# TapuinoMini.net
KiCad netlist of a schematic drawn in EAGLE
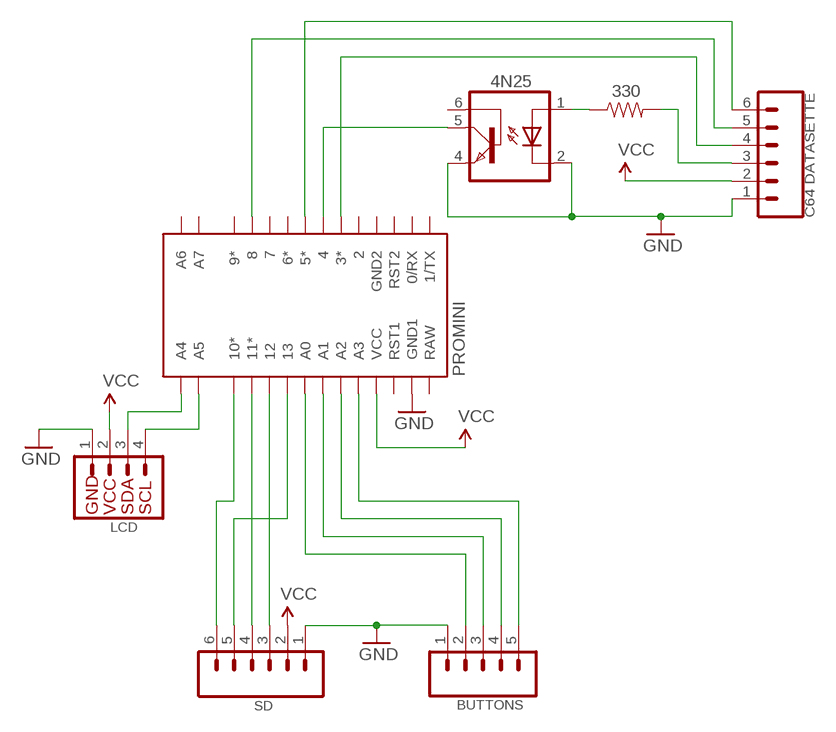
[diagram p0: schematic, sheet 1]

(export (version "E")
  (design (tool "Eeschema 10.0.6"))
  (components
    (comp (ref "JP1")
      (value "C64 DATASETTE")
      (footprint "eagle-import:1X06")
      (libsource (lib "eagle-import") (part "M06SILK_FEMALE_PTH"))
    )
    (comp (ref "JP2")
      (value "SD")
      (footprint "eagle-import:1X06")
      (libsource (lib "eagle-import") (part "M06SILK_FEMALE_PTH"))
    )
    (comp (ref "JP3")
      (value "BUTTONS")
      (footprint "eagle-import:1X05")
      (libsource (lib "eagle-import") (part "M05PTH"))
    )
    (comp (ref "JP4")
      (value "LCD")
      (footprint "eagle-import:1X04")
      (libsource (lib "eagle-import") (part "I2C_STANDARD"))
    )
    (comp (ref "OK1")
      (value "4N25")
      (footprint "eagle-import:DIL06")
      (fields (field (name "MF") "FAIRCHILD SEMICONDUCTOR") (field (name "MPN") "4N35"))
      (libsource (lib "eagle-import") (part "4N35"))
    )
    (comp (ref "PROMINI")
      (value "PROMINI_A")
      (footprint "eagle-import:PROMINI_A")
      (libsource (lib "eagle-import") (part "PROMINI_A"))
    )
    (comp (ref "R1")
      (value "330")
      (footprint "eagle-import:AXIAL-0.3")
      (libsource (lib "eagle-import") (part "RESISTORAXIAL-0.3"))
    )
  )
  (nets
    (net (code "1") (name "GND") (class "Default")
      (node (ref "JP1") (pin "1") (pinfunction "1_1") (pintype "passive"))
      (node (ref "JP2") (pin "1") (pinfunction "1_1") (pintype "passive"))
      (node (ref "JP3") (pin "1") (pinfunction "1_1") (pintype "passive"))
      (node (ref "JP4") (pin "1") (pinfunction "1_1") (pintype "passive"))
      (node (ref "OK1") (pin "2") (pinfunction "C_2") (pintype "passive"))
      (node (ref "OK1") (pin "4") (pinfunction "EMI_4") (pintype "passive"))
      (node (ref "PROMINI") (pin "GND1") (pinfunction "GND1_GND1") (pintype "bidirectional"))
    )
    (net (code "2") (name "Net-(JP1-Pad4)") (class "Default")
      (node (ref "JP1") (pin "4") (pinfunction "4_4") (pintype "passive"))
      (node (ref "PROMINI") (pin "3*") (pinfunction "3*_3*") (pintype "bidirectional"))
    )
    (net (code "3") (name "Net-(JP1-Pad5)") (class "Default")
      (node (ref "JP1") (pin "5") (pinfunction "5_5") (pintype "passive"))
      (node (ref "PROMINI") (pin "8") (pinfunction "8_8") (pintype "bidirectional"))
    )
    (net (code "4") (name "Net-(JP1-Pad6)") (class "Default")
      (node (ref "JP1") (pin "6") (pinfunction "6_6") (pintype "passive"))
      (node (ref "PROMINI") (pin "5*") (pinfunction "5*_5*") (pintype "bidirectional"))
    )
    (net (code "5") (name "Net-(JP2-Pad3)") (class "Default")
      (node (ref "JP2") (pin "3") (pinfunction "3_3") (pintype "passive"))
      (node (ref "PROMINI") (pin "12") (pinfunction "12_12") (pintype "bidirectional"))
    )
    (net (code "6") (name "Net-(JP2-Pad4)") (class "Default")
      (node (ref "JP2") (pin "4") (pinfunction "4_4") (pintype "passive"))
      (node (ref "PROMINI") (pin "11*") (pinfunction "11*_11*") (pintype "bidirectional"))
    )
    (net (code "7") (name "Net-(JP2-Pad5)") (class "Default")
      (node (ref "JP2") (pin "5") (pinfunction "5_5") (pintype "passive"))
      (node (ref "PROMINI") (pin "13") (pinfunction "13_13") (pintype "bidirectional"))
    )
    (net (code "8") (name "Net-(JP2-Pad6)") (class "Default")
      (node (ref "JP2") (pin "6") (pinfunction "6_6") (pintype "passive"))
      (node (ref "PROMINI") (pin "10*") (pinfunction "10*_10*") (pintype "bidirectional"))
    )
    (net (code "9") (name "Net-(JP3-Pad2)") (class "Default")
      (node (ref "JP3") (pin "2") (pinfunction "2_2") (pintype "passive"))
      (node (ref "PROMINI") (pin "A0") (pinfunction "A0_A0") (pintype "bidirectional"))
    )
    (net (code "10") (name "Net-(JP3-Pad3)") (class "Default")
      (node (ref "JP3") (pin "3") (pinfunction "3_3") (pintype "passive"))
      (node (ref "PROMINI") (pin "A1") (pinfunction "A1_A1") (pintype "bidirectional"))
    )
    (net (code "11") (name "Net-(JP3-Pad4)") (class "Default")
      (node (ref "JP3") (pin "4") (pinfunction "4_4") (pintype "passive"))
      (node (ref "PROMINI") (pin "A2") (pinfunction "A2_A2") (pintype "bidirectional"))
    )
    (net (code "12") (name "Net-(JP3-Pad5)") (class "Default")
      (node (ref "JP3") (pin "5") (pinfunction "5_5") (pintype "passive"))
      (node (ref "PROMINI") (pin "A3") (pinfunction "A3_A3") (pintype "bidirectional"))
    )
    (net (code "13") (name "Net-(JP4-Pad3)") (class "Default")
      (node (ref "JP4") (pin "3") (pinfunction "3_3") (pintype "passive"))
      (node (ref "PROMINI") (pin "A4") (pinfunction "A4_A4") (pintype "bidirectional"))
    )
    (net (code "14") (name "Net-(JP4-Pad4)") (class "Default")
      (node (ref "JP4") (pin "4") (pinfunction "4_4") (pintype "passive"))
      (node (ref "PROMINI") (pin "A5") (pinfunction "A5_A5") (pintype "bidirectional"))
    )
    (net (code "15") (name "Net-(OK1-A)") (class "Default")
      (node (ref "OK1") (pin "1") (pinfunction "A_1") (pintype "passive"))
      (node (ref "R1") (pin "P$1") (pinfunction "1_P$1") (pintype "passive"))
    )
    (net (code "16") (name "Net-(OK1-COL)") (class "Default")
      (node (ref "OK1") (pin "5") (pinfunction "COL_5") (pintype "passive"))
      (node (ref "PROMINI") (pin "4") (pinfunction "4_4") (pintype "bidirectional"))
    )
    (net (code "17") (name "Net-(R1-2)") (class "Default")
      (node (ref "JP1") (pin "3") (pinfunction "3_3") (pintype "passive"))
      (node (ref "R1") (pin "P$2") (pinfunction "2_P$2") (pintype "passive"))
    )
    (net (code "18") (name "VCC") (class "Default")
      (node (ref "JP1") (pin "2") (pinfunction "2_2") (pintype "passive"))
      (node (ref "JP2") (pin "2") (pinfunction "2_2") (pintype "passive"))
      (node (ref "JP4") (pin "2") (pinfunction "2_2") (pintype "passive"))
      (node (ref "PROMINI") (pin "VCC") (pinfunction "VCC_VCC") (pintype "bidirectional"))
    )
    (net (code "19") (name "unconnected-(OK1-BAS-Pad6)") (class "Default")
      (node (ref "OK1") (pin "6") (pinfunction "BAS_6") (pintype "passive"))
    )
    (net (code "20") (name "unconnected-(PROMINI-Pad0{slash}RX)") (class "Default")
      (node (ref "PROMINI") (pin "0/RX") (pinfunction "0/RX_0/RX") (pintype "bidirectional"))
    )
    (net (code "21") (name "unconnected-(PROMINI-Pad1{slash}TX)") (class "Default")
      (node (ref "PROMINI") (pin "1/TX") (pinfunction "1/TX_1/TX") (pintype "bidirectional"))
    )
    (net (code "22") (name "unconnected-(PROMINI-Pad2)") (class "Default")
      (node (ref "PROMINI") (pin "2") (pinfunction "2_2") (pintype "bidirectional"))
    )
    (net (code "23") (name "unconnected-(PROMINI-Pad6*)") (class "Default")
      (node (ref "PROMINI") (pin "6*") (pinfunction "6*_6*") (pintype "bidirectional"))
    )
    (net (code "24") (name "unconnected-(PROMINI-Pad7)") (class "Default")
      (node (ref "PROMINI") (pin "7") (pinfunction "7_7") (pintype "bidirectional"))
    )
    (net (code "25") (name "unconnected-(PROMINI-Pad9*)") (class "Default")
      (node (ref "PROMINI") (pin "9*") (pinfunction "9*_9*") (pintype "bidirectional"))
    )
    (net (code "26") (name "unconnected-(PROMINI-PadA6)") (class "Default")
      (node (ref "PROMINI") (pin "A6") (pinfunction "A6_A6") (pintype "bidirectional"))
    )
    (net (code "27") (name "unconnected-(PROMINI-PadA7)") (class "Default")
      (node (ref "PROMINI") (pin "A7") (pinfunction "A7_A7") (pintype "bidirectional"))
    )
    (net (code "28") (name "unconnected-(PROMINI-PadGND2)") (class "Default")
      (node (ref "PROMINI") (pin "GND2") (pinfunction "GND2_GND2") (pintype "bidirectional"))
    )
    (net (code "29") (name "unconnected-(PROMINI-PadRAW)") (class "Default")
      (node (ref "PROMINI") (pin "RAW") (pinfunction "RAW_RAW") (pintype "bidirectional"))
    )
    (net (code "30") (name "unconnected-(PROMINI-PadRST1)") (class "Default")
      (node (ref "PROMINI") (pin "RST1") (pinfunction "RST1_RST1") (pintype "bidirectional"))
    )
    (net (code "31") (name "unconnected-(PROMINI-PadRST2)") (class "Default")
      (node (ref "PROMINI") (pin "RST2") (pinfunction "RST2_RST2") (pintype "bidirectional"))
    )
  )
)
